# wifi_fixer.net
KiCad netlist of a schematic drawn in EAGLE
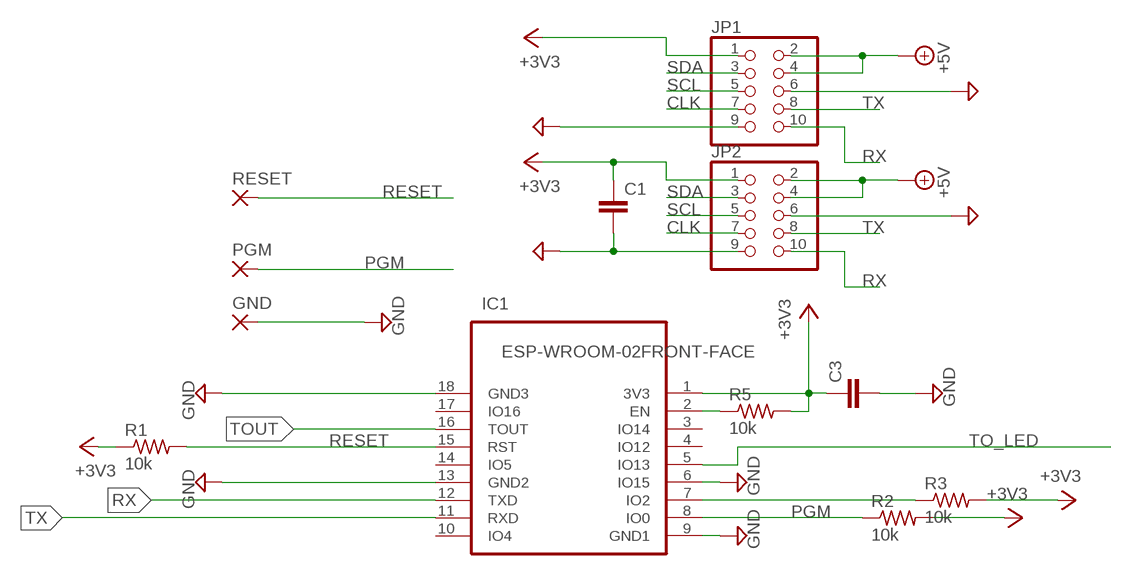
[diagram p0: schematic, sheet 1]

(export (version "E")
  (design (tool "Eeschema 10.0.6"))
  (components
    (comp (ref "C1")
      (value "C-EUC1206")
      (footprint "eagle-import:C1206")
      (libsource (lib "eagle-import") (part "C-EUC1206"))
    )
    (comp (ref "C3")
      (value "C-EUC0603")
      (footprint "eagle-import:C0603")
      (libsource (lib "eagle-import") (part "C-EUC0603"))
    )
    (comp (ref "GND")
      (value "SMD2")
      (footprint "eagle-import:SMD1,27-2,54")
      (libsource (lib "eagle-import") (part "SMD2"))
    )
    (comp (ref "IC1")
      (value "ESP-WROOM-02FRONT-FACE")
      (footprint "eagle-import:FRONT-FACE")
      (libsource (lib "eagle-import") (part "ESP-WROOM-02FRONT-FACE"))
    )
    (comp (ref "JP1")
      (value "PINHD-2X5")
      (footprint "eagle-import:2X05")
      (libsource (lib "eagle-import") (part "PINHD-2X5"))
    )
    (comp (ref "JP2")
      (value "PINHD-2X5")
      (footprint "eagle-import:2X05")
      (libsource (lib "eagle-import") (part "PINHD-2X5"))
    )
    (comp (ref "PGM")
      (value "SMD2")
      (footprint "eagle-import:SMD1,27-2,54")
      (libsource (lib "eagle-import") (part "SMD2"))
    )
    (comp (ref "R1")
      (value "10k")
      (footprint "eagle-import:R0603")
      (libsource (lib "eagle-import") (part "R-US_R0603"))
    )
    (comp (ref "R2")
      (value "10k")
      (footprint "eagle-import:R0603")
      (libsource (lib "eagle-import") (part "R-US_R0603"))
    )
    (comp (ref "R3")
      (value "10k")
      (footprint "eagle-import:R0603")
      (libsource (lib "eagle-import") (part "R-US_R0603"))
    )
    (comp (ref "R5")
      (value "10k")
      (footprint "eagle-import:R0603")
      (libsource (lib "eagle-import") (part "R-US_R0603"))
    )
    (comp (ref "RESET")
      (value "SMD2")
      (footprint "eagle-import:SMD1,27-2,54")
      (libsource (lib "eagle-import") (part "SMD2"))
    )
  )
  (nets
    (net (code "1") (name "+3V3") (class "Default")
      (node (ref "C1") (pin "1") (pinfunction "1_1") (pintype "passive"))
      (node (ref "C3") (pin "1") (pinfunction "1_1") (pintype "passive"))
      (node (ref "IC1") (pin "1") (pinfunction "3V3_1") (pintype "power_in"))
      (node (ref "JP1") (pin "1") (pinfunction "1_1") (pintype "passive"))
      (node (ref "JP2") (pin "1") (pinfunction "1_1") (pintype "passive"))
      (node (ref "R1") (pin "1") (pinfunction "1_1") (pintype "passive"))
      (node (ref "R2") (pin "2") (pinfunction "2_2") (pintype "passive"))
      (node (ref "R3") (pin "2") (pinfunction "2_2") (pintype "passive"))
      (node (ref "R5") (pin "2") (pinfunction "2_2") (pintype "passive"))
    )
    (net (code "2") (name "+5V") (class "Default")
      (node (ref "JP1") (pin "2") (pinfunction "2_2") (pintype "passive"))
      (node (ref "JP1") (pin "4") (pinfunction "4_4") (pintype "passive"))
      (node (ref "JP2") (pin "2") (pinfunction "2_2") (pintype "passive"))
      (node (ref "JP2") (pin "4") (pinfunction "4_4") (pintype "passive"))
    )
    (net (code "3") (name "/CLK") (class "Default")
      (node (ref "JP1") (pin "7") (pinfunction "7_7") (pintype "passive"))
      (node (ref "JP2") (pin "7") (pinfunction "7_7") (pintype "passive"))
    )
    (net (code "4") (name "/PGM") (class "Default")
      (node (ref "IC1") (pin "8") (pinfunction "IO0_8") (pintype "bidirectional"))
      (node (ref "PGM") (pin "1") (pinfunction "P_1") (pintype "passive"))
      (node (ref "R2") (pin "1") (pinfunction "1_1") (pintype "passive"))
    )
    (net (code "5") (name "/RESET") (class "Default")
      (node (ref "IC1") (pin "15") (pinfunction "RST_15") (pintype "bidirectional"))
      (node (ref "R1") (pin "2") (pinfunction "2_2") (pintype "passive"))
      (node (ref "RESET") (pin "1") (pinfunction "P_1") (pintype "passive"))
    )
    (net (code "6") (name "/SCL") (class "Default")
      (node (ref "JP1") (pin "5") (pinfunction "5_5") (pintype "passive"))
      (node (ref "JP2") (pin "5") (pinfunction "5_5") (pintype "passive"))
    )
    (net (code "7") (name "/SDA") (class "Default")
      (node (ref "JP1") (pin "3") (pinfunction "3_3") (pintype "passive"))
      (node (ref "JP2") (pin "3") (pinfunction "3_3") (pintype "passive"))
    )
    (net (code "8") (name "/TO_LED") (class "Default")
      (node (ref "IC1") (pin "5") (pinfunction "IO13_5") (pintype "bidirectional"))
    )
    (net (code "9") (name "GND") (class "Default")
      (node (ref "C1") (pin "2") (pinfunction "2_2") (pintype "passive"))
      (node (ref "C3") (pin "2") (pinfunction "2_2") (pintype "passive"))
      (node (ref "GND") (pin "1") (pinfunction "P_1") (pintype "passive"))
      (node (ref "IC1") (pin "13") (pinfunction "GND2_13") (pintype "power_in"))
      (node (ref "IC1") (pin "18") (pinfunction "GND3_18") (pintype "power_in"))
      (node (ref "IC1") (pin "6") (pinfunction "IO15_6") (pintype "bidirectional"))
      (node (ref "IC1") (pin "9") (pinfunction "GND1_9") (pintype "power_in"))
      (node (ref "JP1") (pin "6") (pinfunction "6_6") (pintype "passive"))
      (node (ref "JP1") (pin "9") (pinfunction "9_9") (pintype "passive"))
      (node (ref "JP2") (pin "6") (pinfunction "6_6") (pintype "passive"))
      (node (ref "JP2") (pin "9") (pinfunction "9_9") (pintype "passive"))
    )
    (net (code "10") (name "Net-(IC1-EN)") (class "Default")
      (node (ref "IC1") (pin "2") (pinfunction "EN_2") (pintype "bidirectional"))
      (node (ref "R5") (pin "1") (pinfunction "1_1") (pintype "passive"))
    )
    (net (code "11") (name "Net-(IC1-IO2)") (class "Default")
      (node (ref "IC1") (pin "7") (pinfunction "IO2_7") (pintype "bidirectional"))
      (node (ref "R3") (pin "1") (pinfunction "1_1") (pintype "passive"))
    )
    (net (code "12") (name "RX") (class "Default")
      (node (ref "IC1") (pin "12") (pinfunction "TXD_12") (pintype "bidirectional"))
      (node (ref "JP1") (pin "10") (pinfunction "10_10") (pintype "passive"))
      (node (ref "JP2") (pin "10") (pinfunction "10_10") (pintype "passive"))
    )
    (net (code "13") (name "TOUT") (class "Default")
      (node (ref "IC1") (pin "16") (pinfunction "TOUT_16") (pintype "bidirectional"))
    )
    (net (code "14") (name "TX") (class "Default")
      (node (ref "IC1") (pin "11") (pinfunction "RXD_11") (pintype "bidirectional"))
      (node (ref "JP1") (pin "8") (pinfunction "8_8") (pintype "passive"))
      (node (ref "JP2") (pin "8") (pinfunction "8_8") (pintype "passive"))
    )
    (net (code "15") (name "unconnected-(IC1-IO4-Pad10)") (class "Default")
      (node (ref "IC1") (pin "10") (pinfunction "IO4_10") (pintype "bidirectional"))
    )
    (net (code "16") (name "unconnected-(IC1-IO5-Pad14)") (class "Default")
      (node (ref "IC1") (pin "14") (pinfunction "IO5_14") (pintype "open_collector"))
    )
    (net (code "17") (name "unconnected-(IC1-IO12-Pad4)") (class "Default")
      (node (ref "IC1") (pin "4") (pinfunction "IO12_4") (pintype "bidirectional"))
    )
    (net (code "18") (name "unconnected-(IC1-IO14-Pad3)") (class "Default")
      (node (ref "IC1") (pin "3") (pinfunction "IO14_3") (pintype "bidirectional"))
    )
    (net (code "19") (name "unconnected-(IC1-IO16-Pad17)") (class "Default")
      (node (ref "IC1") (pin "17") (pinfunction "IO16_17") (pintype "bidirectional"))
    )
  )
)
